# MotorCell_noPow.net
KiCad netlist of a schematic drawn in Altium Designer
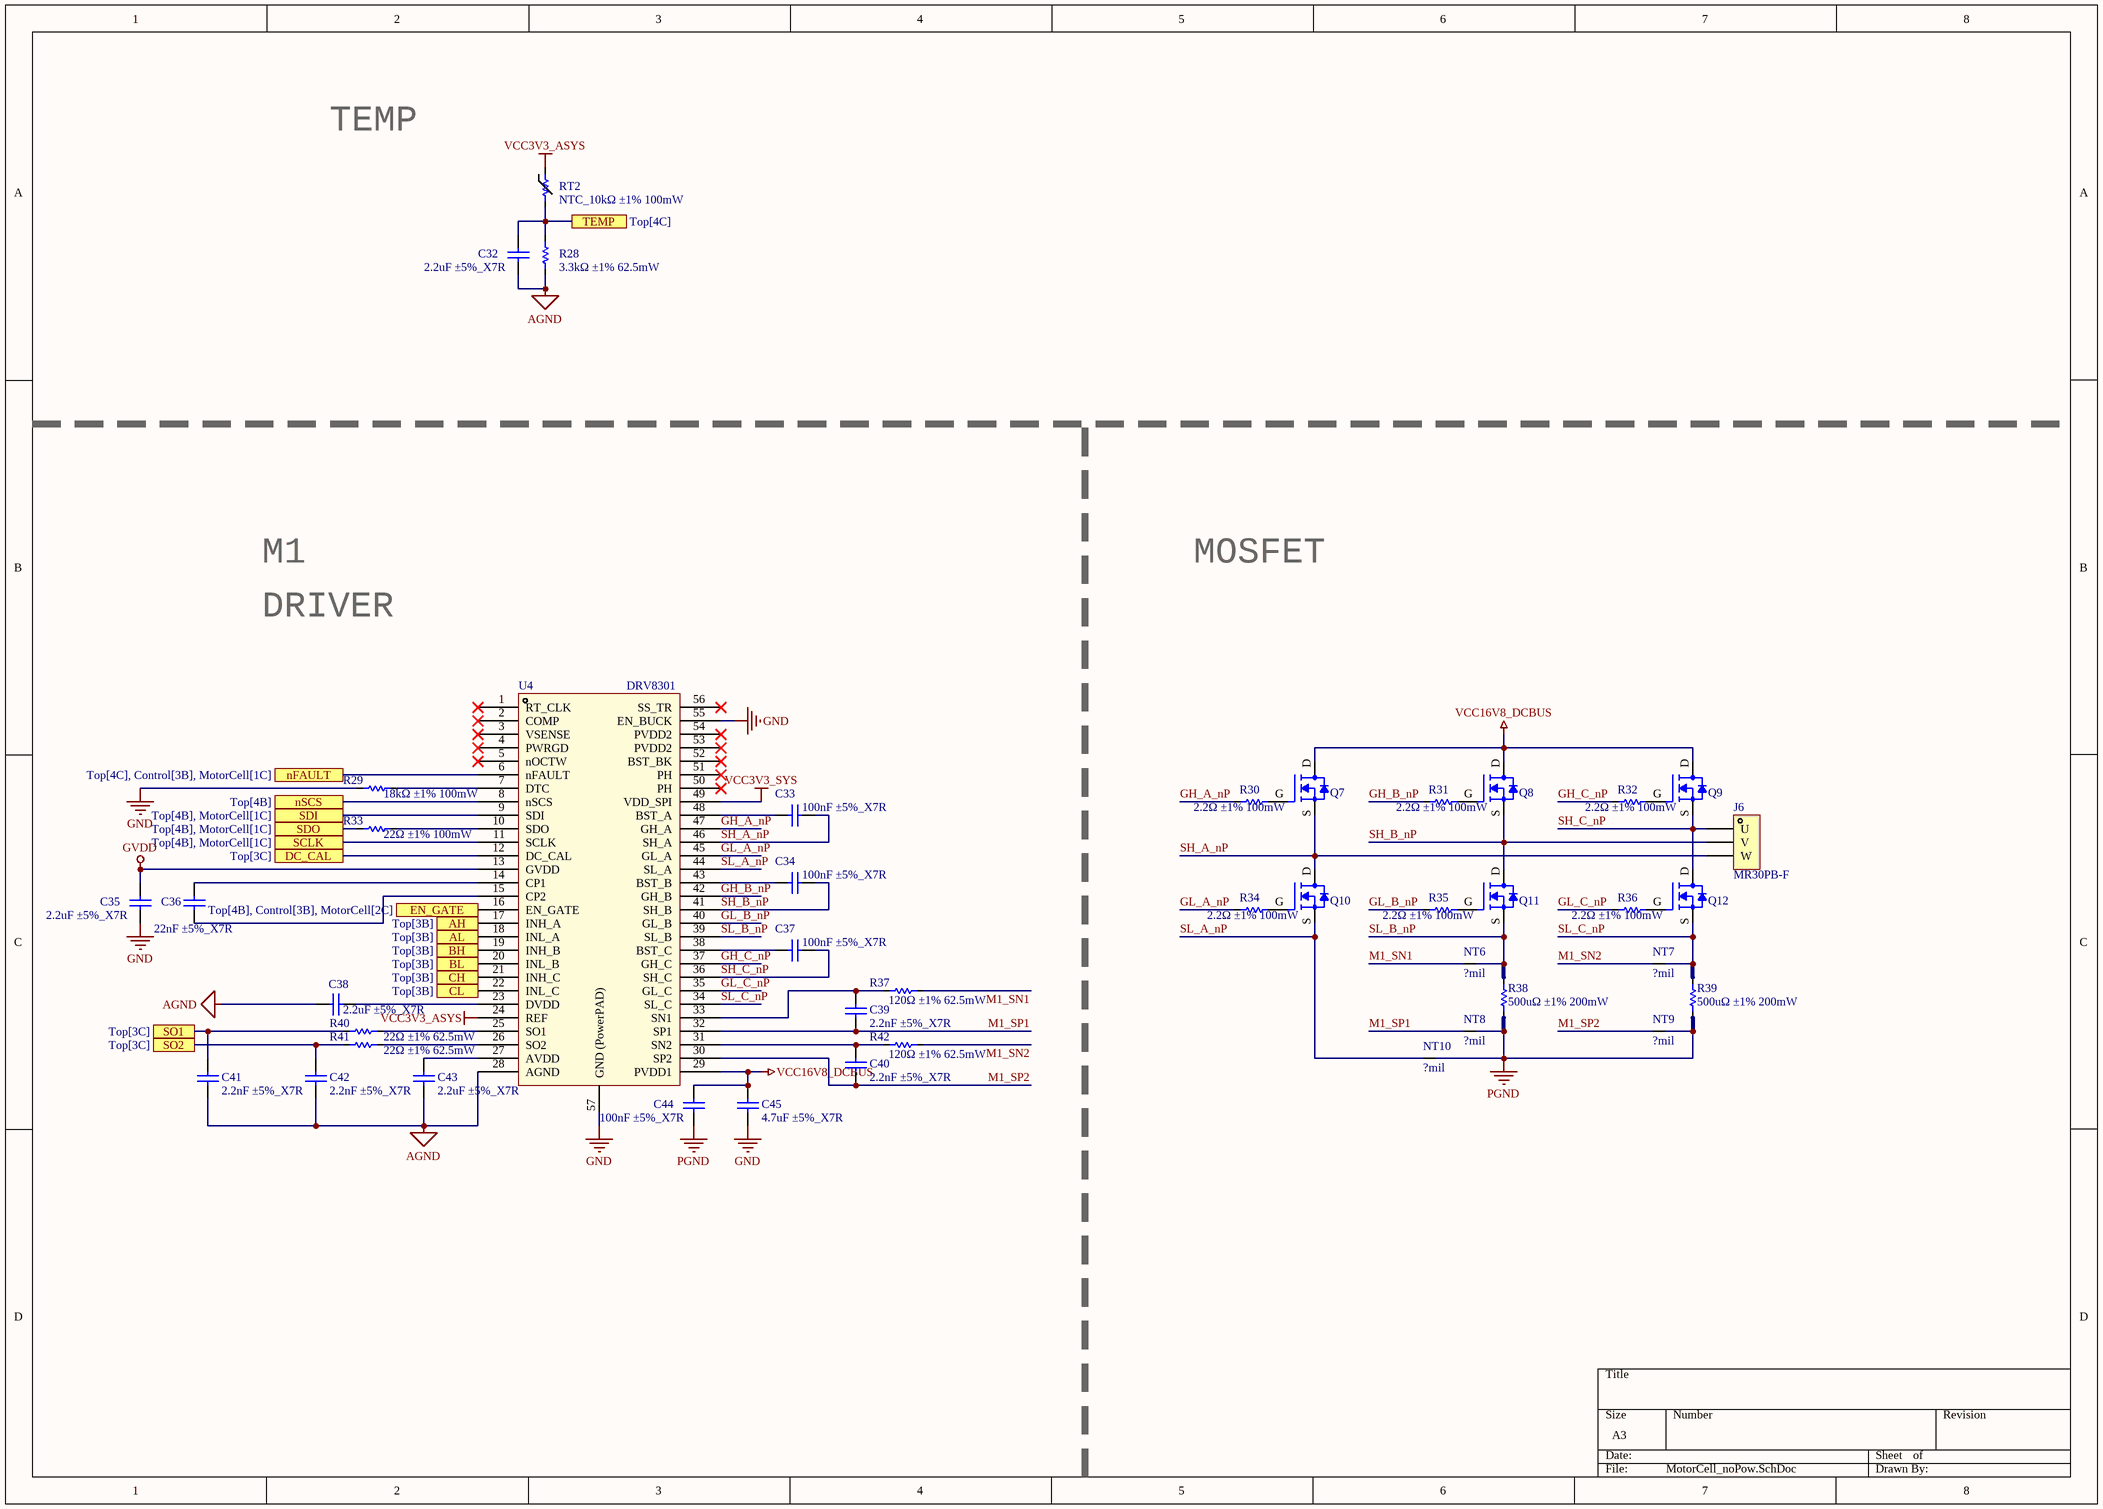
[diagram p0: MotorCell_noPow.SchDoc]

(export (version "E")
  (design (tool "Eeschema 10.0.6"))
  (components
    (comp (ref "C32")
      (value "2.2uF ±5%_X7R")
      (footprint "C0402")
      (description "Capacitor")
      (fields (field (name "PUBLISHER") "Altium Limited"))
      (libsource (lib "Component") (part "Cap"))
    )
    (comp (ref "C33")
      (value "100nF ±5%_X7R")
      (footprint "C0402")
      (description "Capacitor")
      (fields (field (name "PUBLISHER") "Altium Limited"))
      (libsource (lib "Component") (part "Cap"))
    )
    (comp (ref "C34")
      (value "100nF ±5%_X7R")
      (footprint "C0402")
      (description "Capacitor")
      (fields (field (name "PUBLISHER") "Altium Limited"))
      (libsource (lib "Component") (part "Cap"))
    )
    (comp (ref "C35")
      (value "2.2uF ±5%_X7R")
      (footprint "C0603")
      (description "Capacitor")
      (fields (field (name "PUBLISHER") "Altium Limited"))
      (libsource (lib "Component") (part "Cap"))
    )
    (comp (ref "C36")
      (value "22nF ±5%_X7R")
      (footprint "C0402")
      (description "Capacitor")
      (fields (field (name "PUBLISHER") "Altium Limited"))
      (libsource (lib "Component") (part "Cap"))
    )
    (comp (ref "C37")
      (value "100nF ±5%_X7R")
      (footprint "C0402")
      (description "Capacitor")
      (fields (field (name "PUBLISHER") "Altium Limited"))
      (libsource (lib "Component") (part "Cap"))
    )
    (comp (ref "C38")
      (value "2.2uF ±5%_X7R")
      (footprint "C0603")
      (description "Capacitor")
      (fields (field (name "PUBLISHER") "Altium Limited"))
      (libsource (lib "Component") (part "Cap"))
    )
    (comp (ref "C39")
      (value "2.2nF ±5%_X7R")
      (footprint "C0402")
      (description "Capacitor")
      (fields (field (name "PUBLISHER") "Altium Limited"))
      (libsource (lib "Component") (part "Cap"))
    )
    (comp (ref "C40")
      (value "2.2nF ±5%_X7R")
      (footprint "C0402")
      (description "Capacitor")
      (fields (field (name "PUBLISHER") "Altium Limited"))
      (libsource (lib "Component") (part "Cap"))
    )
    (comp (ref "C41")
      (value "2.2nF ±5%_X7R")
      (footprint "C0402")
      (description "Capacitor")
      (fields (field (name "PUBLISHER") "Altium Limited"))
      (libsource (lib "Component") (part "Cap"))
    )
    (comp (ref "C42")
      (value "2.2nF ±5%_X7R")
      (footprint "C0402")
      (description "Capacitor")
      (fields (field (name "PUBLISHER") "Altium Limited"))
      (libsource (lib "Component") (part "Cap"))
    )
    (comp (ref "C43")
      (value "2.2uF ±5%_X7R")
      (footprint "C0603")
      (description "Capacitor")
      (fields (field (name "PUBLISHER") "Altium Limited"))
      (libsource (lib "Component") (part "Cap"))
    )
    (comp (ref "C44")
      (value "100nF ±5%_X7R")
      (footprint "C0402")
      (description "Capacitor")
      (fields (field (name "PUBLISHER") "Altium Limited"))
      (libsource (lib "Component") (part "Cap"))
    )
    (comp (ref "C45")
      (value "4.7uF ±5%_X7R")
      (footprint "C0603")
      (description "Capacitor")
      (fields (field (name "PUBLISHER") "Altium Limited"))
      (libsource (lib "Component") (part "Cap"))
    )
    (comp (ref "J6")
      (value "MR30PB-F")
      (footprint "MR30PB-F [Straight] [SMT]")
      (description "驱动器端")
      (libsource (lib "Connectivity_Plugs") (part "MR30PB-F [Straight] [SMT]"))
    )
    (comp (ref "NT6") (value "?mil") (footprint "NETTIE_8mil") (libsource (lib "Component") (part "NETTIE")))
    (comp (ref "NT7") (value "?mil") (footprint "NETTIE_8mil") (libsource (lib "Component") (part "NETTIE")))
    (comp (ref "NT8") (value "?mil") (footprint "NETTIE_8mil") (libsource (lib "Component") (part "NETTIE")))
    (comp (ref "NT9") (value "?mil") (footprint "NETTIE_8mil") (libsource (lib "Component") (part "NETTIE")))
    (comp (ref "NT10") (value "?mil") (footprint "NETTIE_8mil") (libsource (lib "Component") (part "NETTIE")))
    (comp (ref "Q7")
      (value "NTMFS4935NT1G")
      (footprint "NRVTS10100EMFST1G")
      (description "MOSFET – Power, Single,\r\nN-Channel, SO-8 FL\r\n30 V, 93 A")
      (fields (field (name "MANUFACTURER") "ON Semiconductor"))
      (libsource (lib "Component") (part "MOSFET-N"))
    )
    (comp (ref "Q8")
      (value "NTMFS4935NT1G")
      (footprint "NRVTS10100EMFST1G")
      (description "MOSFET – Power, Single,\r\nN-Channel, SO-8 FL\r\n30 V, 93 A")
      (fields (field (name "MANUFACTURER") "ON Semiconductor"))
      (libsource (lib "Component") (part "MOSFET-N"))
    )
    (comp (ref "Q9")
      (value "NTMFS4935NT1G")
      (footprint "NRVTS10100EMFST1G")
      (description "MOSFET – Power, Single,\r\nN-Channel, SO-8 FL\r\n30 V, 93 A")
      (fields (field (name "MANUFACTURER") "ON Semiconductor"))
      (libsource (lib "Component") (part "MOSFET-N"))
    )
    (comp (ref "Q10")
      (value "NTMFS4935NT1G")
      (footprint "NRVTS10100EMFST1G")
      (description "MOSFET – Power, Single,\r\nN-Channel, SO-8 FL\r\n30 V, 93 A")
      (fields (field (name "MANUFACTURER") "ON Semiconductor"))
      (libsource (lib "Component") (part "MOSFET-N"))
    )
    (comp (ref "Q11")
      (value "NTMFS4935NT1G")
      (footprint "NRVTS10100EMFST1G")
      (description "MOSFET – Power, Single,\r\nN-Channel, SO-8 FL\r\n30 V, 93 A")
      (fields (field (name "MANUFACTURER") "ON Semiconductor"))
      (libsource (lib "Component") (part "MOSFET-N"))
    )
    (comp (ref "Q12")
      (value "NTMFS4935NT1G")
      (footprint "NRVTS10100EMFST1G")
      (description "MOSFET – Power, Single,\r\nN-Channel, SO-8 FL\r\n30 V, 93 A")
      (fields (field (name "MANUFACTURER") "ON Semiconductor"))
      (libsource (lib "Component") (part "MOSFET-N"))
    )
    (comp (ref "R28")
      (value "3.3kΩ ±1% 62.5mW")
      (footprint "R0402")
      (description "Resistor")
      (fields (field (name "PUBLISHER") "Altium Limited"))
      (libsource (lib "Component") (part "Res"))
    )
    (comp (ref "R29")
      (value "18kΩ ±1% 100mW")
      (footprint "R0402")
      (description "Resistor")
      (fields (field (name "PUBLISHER") "Altium Limited"))
      (libsource (lib "Component") (part "Res"))
    )
    (comp (ref "R30")
      (value "2.2Ω ±1% 100mW")
      (footprint "R0402")
      (description "Resistor")
      (fields (field (name "PUBLISHER") "Altium Limited"))
      (libsource (lib "Component") (part "Res"))
    )
    (comp (ref "R31")
      (value "2.2Ω ±1% 100mW")
      (footprint "R0402")
      (description "Resistor")
      (fields (field (name "PUBLISHER") "Altium Limited"))
      (libsource (lib "Component") (part "Res"))
    )
    (comp (ref "R32")
      (value "2.2Ω ±1% 100mW")
      (footprint "R0402")
      (description "Resistor")
      (fields (field (name "PUBLISHER") "Altium Limited"))
      (libsource (lib "Component") (part "Res"))
    )
    (comp (ref "R33")
      (value "22Ω ±1% 100mW")
      (footprint "R0402")
      (description "Resistor")
      (fields (field (name "PUBLISHER") "Altium Limited"))
      (libsource (lib "Component") (part "Res"))
    )
    (comp (ref "R34")
      (value "2.2Ω ±1% 100mW")
      (footprint "R0402")
      (description "Resistor")
      (fields (field (name "PUBLISHER") "Altium Limited"))
      (libsource (lib "Component") (part "Res"))
    )
    (comp (ref "R35")
      (value "2.2Ω ±1% 100mW")
      (footprint "R0402")
      (description "Resistor")
      (fields (field (name "PUBLISHER") "Altium Limited"))
      (libsource (lib "Component") (part "Res"))
    )
    (comp (ref "R36")
      (value "2.2Ω ±1% 100mW")
      (footprint "R0402")
      (description "Resistor")
      (fields (field (name "PUBLISHER") "Altium Limited"))
      (libsource (lib "Component") (part "Res"))
    )
    (comp (ref "R37")
      (value "120Ω ±1% 62.5mW")
      (footprint "R0402")
      (description "Resistor")
      (fields (field (name "PUBLISHER") "Altium Limited"))
      (libsource (lib "Component") (part "Res"))
    )
    (comp (ref "R38")
      (value "500uΩ ±1% 200mW")
      (footprint "R2512")
      (description "Resistor")
      (fields (field (name "PUBLISHER") "Altium Limited"))
      (libsource (lib "Component") (part "Res"))
    )
    (comp (ref "R39")
      (value "500uΩ ±1% 200mW")
      (footprint "R2512")
      (description "Resistor")
      (fields (field (name "PUBLISHER") "Altium Limited"))
      (libsource (lib "Component") (part "Res"))
    )
    (comp (ref "R40")
      (value "22Ω ±1% 62.5mW")
      (footprint "R0402")
      (description "Resistor")
      (fields (field (name "PUBLISHER") "Altium Limited"))
      (libsource (lib "Component") (part "Res"))
    )
    (comp (ref "R41")
      (value "22Ω ±1% 62.5mW")
      (footprint "R0402")
      (description "Resistor")
      (fields (field (name "PUBLISHER") "Altium Limited"))
      (libsource (lib "Component") (part "Res"))
    )
    (comp (ref "R42")
      (value "120Ω ±1% 62.5mW")
      (footprint "R0402")
      (description "Resistor")
      (fields (field (name "PUBLISHER") "Altium Limited"))
      (libsource (lib "Component") (part "Res"))
    )
    (comp (ref "RT2")
      (value "NTC_10kΩ ±1% 100mW")
      (footprint "R0402")
      (description "THERMISTOR 10K OHM NTC 0402 SMD")
      (libsource (lib "Component") (part "TEMP RES"))
    )
    (comp (ref "U4")
      (value "DRV8301")
      (footprint "TSSOP50P810X120_HS-57N")
      (description "MOTOR DRIVER, 3PH, 56HTSSOP")
      (libsource (lib "IC") (part "DRV8301"))
    )
  )
  (nets
    (net (code "1") (name "/AH") (class "Default")
      (node (ref "U4") (pin "17") (pinfunction "INH_A_17") (pintype "passive"))
    )
    (net (code "2") (name "/AL") (class "Default")
      (node (ref "U4") (pin "18") (pinfunction "INL_A_18") (pintype "passive"))
    )
    (net (code "3") (name "/BH") (class "Default")
      (node (ref "U4") (pin "19") (pinfunction "INH_B_19") (pintype "passive"))
    )
    (net (code "4") (name "/BL") (class "Default")
      (node (ref "U4") (pin "20") (pinfunction "INL_B_20") (pintype "passive"))
    )
    (net (code "5") (name "/CH") (class "Default")
      (node (ref "U4") (pin "21") (pinfunction "INH_C_21") (pintype "passive"))
    )
    (net (code "6") (name "/CL") (class "Default")
      (node (ref "U4") (pin "22") (pinfunction "INL_C_22") (pintype "passive"))
    )
    (net (code "7") (name "/DC_CAL") (class "Default")
      (node (ref "U4") (pin "12") (pinfunction "DC_CAL_12") (pintype "passive"))
    )
    (net (code "8") (name "/EN_GATE") (class "Default")
      (node (ref "U4") (pin "16") (pinfunction "EN_GATE_16") (pintype "passive"))
    )
    (net (code "9") (name "/GH_A_nP") (class "Default")
      (node (ref "R30") (pin "2") (pinfunction "2_2") (pintype "passive"))
      (node (ref "U4") (pin "47") (pinfunction "GH_A_47") (pintype "passive"))
    )
    (net (code "10") (name "/GH_B_nP") (class "Default")
      (node (ref "R31") (pin "2") (pinfunction "2_2") (pintype "passive"))
      (node (ref "U4") (pin "42") (pinfunction "GH_B_42") (pintype "passive"))
    )
    (net (code "11") (name "/GH_C_nP") (class "Default")
      (node (ref "R32") (pin "2") (pinfunction "2_2") (pintype "passive"))
      (node (ref "U4") (pin "37") (pinfunction "GH_C_37") (pintype "passive"))
    )
    (net (code "12") (name "/GL_A_nP") (class "Default")
      (node (ref "R34") (pin "2") (pinfunction "2_2") (pintype "passive"))
      (node (ref "U4") (pin "45") (pinfunction "GL_A_45") (pintype "passive"))
    )
    (net (code "13") (name "/GL_B_nP") (class "Default")
      (node (ref "R35") (pin "2") (pinfunction "2_2") (pintype "passive"))
      (node (ref "U4") (pin "40") (pinfunction "GL_B_40") (pintype "passive"))
    )
    (net (code "14") (name "/GL_C_nP") (class "Default")
      (node (ref "R36") (pin "2") (pinfunction "2_2") (pintype "passive"))
      (node (ref "U4") (pin "35") (pinfunction "GL_C_35") (pintype "passive"))
    )
    (net (code "15") (name "/M1_SN1") (class "Default")
      (node (ref "NT6") (pin "1") (pinfunction "1_1") (pintype "passive"))
      (node (ref "R37") (pin "1") (pinfunction "1_1") (pintype "passive"))
    )
    (net (code "16") (name "/M1_SN2") (class "Default")
      (node (ref "NT7") (pin "1") (pinfunction "1_1") (pintype "passive"))
      (node (ref "R42") (pin "1") (pinfunction "1_1") (pintype "passive"))
    )
    (net (code "17") (name "/M1_SP1") (class "Default")
      (node (ref "C39") (pin "1") (pinfunction "1_1") (pintype "passive"))
      (node (ref "NT8") (pin "1") (pinfunction "1_1") (pintype "passive"))
      (node (ref "U4") (pin "32") (pinfunction "SP1_32") (pintype "passive"))
    )
    (net (code "18") (name "/M1_SP2") (class "Default")
      (node (ref "C40") (pin "1") (pinfunction "1_1") (pintype "passive"))
      (node (ref "NT9") (pin "1") (pinfunction "1_1") (pintype "passive"))
      (node (ref "U4") (pin "30") (pinfunction "SP2_30") (pintype "passive"))
    )
    (net (code "19") (name "/SCLK") (class "Default")
      (node (ref "U4") (pin "11") (pinfunction "SCLK_11") (pintype "passive"))
    )
    (net (code "20") (name "/SDI") (class "Default")
      (node (ref "U4") (pin "9") (pinfunction "SDI_9") (pintype "passive"))
    )
    (net (code "21") (name "/SDO") (class "Default")
      (node (ref "R33") (pin "1") (pinfunction "1_1") (pintype "passive"))
    )
    (net (code "22") (name "/SH_A_nP") (class "Default")
      (node (ref "C33") (pin "1") (pinfunction "1_1") (pintype "passive"))
      (node (ref "J6") (pin "3") (pinfunction "W_3") (pintype "passive"))
      (node (ref "Q10") (pin "D") (pinfunction "D_D") (pintype "passive"))
      (node (ref "Q7") (pin "S") (pinfunction "S_S") (pintype "passive"))
      (node (ref "U4") (pin "46") (pinfunction "SH_A_46") (pintype "passive"))
    )
    (net (code "23") (name "/SH_B_nP") (class "Default")
      (node (ref "C34") (pin "1") (pinfunction "1_1") (pintype "passive"))
      (node (ref "J6") (pin "2") (pinfunction "V_2") (pintype "passive"))
      (node (ref "Q11") (pin "D") (pinfunction "D_D") (pintype "passive"))
      (node (ref "Q8") (pin "S") (pinfunction "S_S") (pintype "passive"))
      (node (ref "U4") (pin "41") (pinfunction "SH_B_41") (pintype "passive"))
    )
    (net (code "24") (name "/SH_C_nP") (class "Default")
      (node (ref "C37") (pin "1") (pinfunction "1_1") (pintype "passive"))
      (node (ref "J6") (pin "1") (pinfunction "U_1") (pintype "passive"))
      (node (ref "Q12") (pin "D") (pinfunction "D_D") (pintype "passive"))
      (node (ref "Q9") (pin "S") (pinfunction "S_S") (pintype "passive"))
      (node (ref "U4") (pin "36") (pinfunction "SH_C_36") (pintype "passive"))
    )
    (net (code "25") (name "/SL_A_nP") (class "Default")
      (node (ref "NT10") (pin "2") (pinfunction "2_2") (pintype "passive"))
      (node (ref "Q10") (pin "S") (pinfunction "S_S") (pintype "passive"))
      (node (ref "U4") (pin "44") (pinfunction "SL_A_44") (pintype "passive"))
    )
    (net (code "26") (name "/SL_B_nP") (class "Default")
      (node (ref "NT6") (pin "2") (pinfunction "2_2") (pintype "passive"))
      (node (ref "Q11") (pin "S") (pinfunction "S_S") (pintype "passive"))
      (node (ref "R38") (pin "2") (pinfunction "2_2") (pintype "passive"))
      (node (ref "U4") (pin "39") (pinfunction "SL_B_39") (pintype "passive"))
    )
    (net (code "27") (name "/SL_C_nP") (class "Default")
      (node (ref "NT7") (pin "2") (pinfunction "2_2") (pintype "passive"))
      (node (ref "Q12") (pin "S") (pinfunction "S_S") (pintype "passive"))
      (node (ref "R39") (pin "2") (pinfunction "2_2") (pintype "passive"))
      (node (ref "U4") (pin "34") (pinfunction "SL_C_34") (pintype "passive"))
    )
    (net (code "28") (name "/SO1") (class "Default")
      (node (ref "C41") (pin "2") (pinfunction "2_2") (pintype "passive"))
      (node (ref "R40") (pin "2") (pinfunction "2_2") (pintype "passive"))
    )
    (net (code "29") (name "/SO2") (class "Default")
      (node (ref "C42") (pin "2") (pinfunction "2_2") (pintype "passive"))
      (node (ref "R41") (pin "2") (pinfunction "2_2") (pintype "passive"))
    )
    (net (code "30") (name "/TEMP") (class "Default")
      (node (ref "C32") (pin "2") (pinfunction "2_2") (pintype "passive"))
      (node (ref "R28") (pin "2") (pinfunction "2_2") (pintype "passive"))
      (node (ref "RT2") (pin "2") (pinfunction "2_2") (pintype "passive"))
    )
    (net (code "31") (name "/nFAULT") (class "Default")
      (node (ref "U4") (pin "6") (pinfunction "nFAULT_6") (pintype "passive"))
    )
    (net (code "32") (name "/nSCS") (class "Default")
      (node (ref "U4") (pin "8") (pinfunction "nSCS_8") (pintype "passive"))
    )
    (net (code "33") (name "AGND") (class "Default")
      (node (ref "C32") (pin "1") (pinfunction "1_1") (pintype "passive"))
      (node (ref "C38") (pin "2") (pinfunction "2_2") (pintype "passive"))
      (node (ref "C41") (pin "1") (pinfunction "1_1") (pintype "passive"))
      (node (ref "C42") (pin "1") (pinfunction "1_1") (pintype "passive"))
      (node (ref "C43") (pin "1") (pinfunction "1_1") (pintype "passive"))
      (node (ref "R28") (pin "1") (pinfunction "1_1") (pintype "passive"))
      (node (ref "U4") (pin "28") (pinfunction "AGND_28") (pintype "passive"))
    )
    (net (code "34") (name "GND") (class "Default")
      (node (ref "C35") (pin "1") (pinfunction "1_1") (pintype "passive"))
      (node (ref "C45") (pin "1") (pinfunction "1_1") (pintype "passive"))
      (node (ref "R29") (pin "2") (pinfunction "2_2") (pintype "passive"))
      (node (ref "U4") (pin "55") (pinfunction "EN_BUCK_55") (pintype "passive"))
      (node (ref "U4") (pin "57") (pinfunction "GND_(PowerPAD)_57") (pintype "passive"))
    )
    (net (code "35") (name "GVDD") (class "Default")
      (node (ref "C35") (pin "2") (pinfunction "2_2") (pintype "passive"))
      (node (ref "U4") (pin "13") (pinfunction "GVDD_13") (pintype "passive"))
    )
    (net (code "36") (name "Net-(Q7-PadG)") (class "Default")
      (node (ref "Q7") (pin "G") (pinfunction "G_G") (pintype "passive"))
      (node (ref "R30") (pin "1") (pinfunction "1_1") (pintype "passive"))
    )
    (net (code "37") (name "Net-(Q8-PadG)") (class "Default")
      (node (ref "Q8") (pin "G") (pinfunction "G_G") (pintype "passive"))
      (node (ref "R31") (pin "1") (pinfunction "1_1") (pintype "passive"))
    )
    (net (code "38") (name "Net-(Q9-PadG)") (class "Default")
      (node (ref "Q9") (pin "G") (pinfunction "G_G") (pintype "passive"))
      (node (ref "R32") (pin "1") (pinfunction "1_1") (pintype "passive"))
    )
    (net (code "39") (name "Net-(Q10-PadG)") (class "Default")
      (node (ref "Q10") (pin "G") (pinfunction "G_G") (pintype "passive"))
      (node (ref "R34") (pin "1") (pinfunction "1_1") (pintype "passive"))
    )
    (net (code "40") (name "Net-(Q11-PadG)") (class "Default")
      (node (ref "Q11") (pin "G") (pinfunction "G_G") (pintype "passive"))
      (node (ref "R35") (pin "1") (pinfunction "1_1") (pintype "passive"))
    )
    (net (code "41") (name "Net-(Q12-PadG)") (class "Default")
      (node (ref "Q12") (pin "G") (pinfunction "G_G") (pintype "passive"))
      (node (ref "R36") (pin "1") (pinfunction "1_1") (pintype "passive"))
    )
    (net (code "42") (name "Net-(U4-AVDD)") (class "Default")
      (node (ref "C43") (pin "2") (pinfunction "2_2") (pintype "passive"))
      (node (ref "U4") (pin "27") (pinfunction "AVDD_27") (pintype "passive"))
    )
    (net (code "43") (name "Net-(U4-BST_A)") (class "Default")
      (node (ref "C33") (pin "2") (pinfunction "2_2") (pintype "passive"))
      (node (ref "U4") (pin "48") (pinfunction "BST_A_48") (pintype "passive"))
    )
    (net (code "44") (name "Net-(U4-BST_B)") (class "Default")
      (node (ref "C34") (pin "2") (pinfunction "2_2") (pintype "passive"))
      (node (ref "U4") (pin "43") (pinfunction "BST_B_43") (pintype "passive"))
    )
    (net (code "45") (name "Net-(U4-BST_C)") (class "Default")
      (node (ref "C37") (pin "2") (pinfunction "2_2") (pintype "passive"))
      (node (ref "U4") (pin "38") (pinfunction "BST_C_38") (pintype "passive"))
    )
    (net (code "46") (name "Net-(U4-CP1)") (class "Default")
      (node (ref "C36") (pin "1") (pinfunction "1_1") (pintype "passive"))
      (node (ref "U4") (pin "14") (pinfunction "CP1_14") (pintype "passive"))
    )
    (net (code "47") (name "Net-(U4-CP2)") (class "Default")
      (node (ref "C36") (pin "2") (pinfunction "2_2") (pintype "passive"))
      (node (ref "U4") (pin "15") (pinfunction "CP2_15") (pintype "passive"))
    )
    (net (code "48") (name "Net-(U4-DTC)") (class "Default")
      (node (ref "R29") (pin "1") (pinfunction "1_1") (pintype "passive"))
      (node (ref "U4") (pin "7") (pinfunction "DTC_7") (pintype "passive"))
    )
    (net (code "49") (name "Net-(U4-DVDD)") (class "Default")
      (node (ref "C38") (pin "1") (pinfunction "1_1") (pintype "passive"))
      (node (ref "U4") (pin "23") (pinfunction "DVDD_23") (pintype "passive"))
    )
    (net (code "50") (name "Net-(U4-SDO)") (class "Default")
      (node (ref "R33") (pin "2") (pinfunction "2_2") (pintype "passive"))
      (node (ref "U4") (pin "10") (pinfunction "SDO_10") (pintype "passive"))
    )
    (net (code "51") (name "Net-(U4-SN1)") (class "Default")
      (node (ref "C39") (pin "2") (pinfunction "2_2") (pintype "passive"))
      (node (ref "R37") (pin "2") (pinfunction "2_2") (pintype "passive"))
      (node (ref "U4") (pin "33") (pinfunction "SN1_33") (pintype "passive"))
    )
    (net (code "52") (name "Net-(U4-SN2)") (class "Default")
      (node (ref "C40") (pin "2") (pinfunction "2_2") (pintype "passive"))
      (node (ref "R42") (pin "2") (pinfunction "2_2") (pintype "passive"))
      (node (ref "U4") (pin "31") (pinfunction "SN2_31") (pintype "passive"))
    )
    (net (code "53") (name "Net-(U4-SO1)") (class "Default")
      (node (ref "R40") (pin "1") (pinfunction "1_1") (pintype "passive"))
      (node (ref "U4") (pin "25") (pinfunction "SO1_25") (pintype "passive"))
    )
    (net (code "54") (name "Net-(U4-SO2)") (class "Default")
      (node (ref "R41") (pin "1") (pinfunction "1_1") (pintype "passive"))
      (node (ref "U4") (pin "26") (pinfunction "SO2_26") (pintype "passive"))
    )
    (net (code "55") (name "PGND") (class "Default")
      (node (ref "C44") (pin "1") (pinfunction "1_1") (pintype "passive"))
      (node (ref "NT10") (pin "1") (pinfunction "1_1") (pintype "passive"))
      (node (ref "NT8") (pin "2") (pinfunction "2_2") (pintype "passive"))
      (node (ref "NT9") (pin "2") (pinfunction "2_2") (pintype "passive"))
      (node (ref "R38") (pin "1") (pinfunction "1_1") (pintype "passive"))
      (node (ref "R39") (pin "1") (pinfunction "1_1") (pintype "passive"))
    )
    (net (code "56") (name "VCC3V3_ASYS") (class "Default")
      (node (ref "RT2") (pin "1") (pinfunction "1_1") (pintype "passive"))
      (node (ref "U4") (pin "24") (pinfunction "REF_24") (pintype "passive"))
    )
    (net (code "57") (name "VCC3V3_SYS") (class "Default")
      (node (ref "U4") (pin "49") (pinfunction "VDD_SPI_49") (pintype "passive"))
    )
    (net (code "58") (name "VCC16V8_DCBUS") (class "Default")
      (node (ref "C44") (pin "2") (pinfunction "2_2") (pintype "passive"))
      (node (ref "C45") (pin "2") (pinfunction "2_2") (pintype "passive"))
      (node (ref "Q7") (pin "D") (pinfunction "D_D") (pintype "passive"))
      (node (ref "Q8") (pin "D") (pinfunction "D_D") (pintype "passive"))
      (node (ref "Q9") (pin "D") (pinfunction "D_D") (pintype "passive"))
      (node (ref "U4") (pin "29") (pinfunction "PVDD1_29") (pintype "passive"))
    )
    (net (code "59") (name "unconnected-(U4-BST_BK-Pad52)") (class "Default")
      (node (ref "U4") (pin "52") (pinfunction "BST_BK_52") (pintype "passive+no_connect"))
    )
    (net (code "60") (name "unconnected-(U4-COMP-Pad2)") (class "Default")
      (node (ref "U4") (pin "2") (pinfunction "COMP_2") (pintype "passive+no_connect"))
    )
    (net (code "61") (name "unconnected-(U4-PH-Pad50)") (class "Default")
      (node (ref "U4") (pin "50") (pinfunction "PH_50") (pintype "passive+no_connect"))
    )
    (net (code "62") (name "unconnected-(U4-PH-Pad51)") (class "Default")
      (node (ref "U4") (pin "51") (pinfunction "PH_51") (pintype "passive+no_connect"))
    )
    (net (code "63") (name "unconnected-(U4-PVDD2-Pad53)") (class "Default")
      (node (ref "U4") (pin "53") (pinfunction "PVDD2_53") (pintype "passive+no_connect"))
    )
    (net (code "64") (name "unconnected-(U4-PVDD2-Pad54)") (class "Default")
      (node (ref "U4") (pin "54") (pinfunction "PVDD2_54") (pintype "passive+no_connect"))
    )
    (net (code "65") (name "unconnected-(U4-PWRGD-Pad4)") (class "Default")
      (node (ref "U4") (pin "4") (pinfunction "PWRGD_4") (pintype "passive+no_connect"))
    )
    (net (code "66") (name "unconnected-(U4-RT_CLK-Pad1)") (class "Default")
      (node (ref "U4") (pin "1") (pinfunction "RT_CLK_1") (pintype "passive+no_connect"))
    )
    (net (code "67") (name "unconnected-(U4-SS_TR-Pad56)") (class "Default")
      (node (ref "U4") (pin "56") (pinfunction "SS_TR_56") (pintype "passive+no_connect"))
    )
    (net (code "68") (name "unconnected-(U4-VSENSE-Pad3)") (class "Default")
      (node (ref "U4") (pin "3") (pinfunction "VSENSE_3") (pintype "passive+no_connect"))
    )
    (net (code "69") (name "unconnected-(U4-nOCTW-Pad5)") (class "Default")
      (node (ref "U4") (pin "5") (pinfunction "nOCTW_5") (pintype "passive+no_connect"))
    )
  )
)
